# Simple_LED.net
KiCad netlist of a schematic drawn in Altium Designer
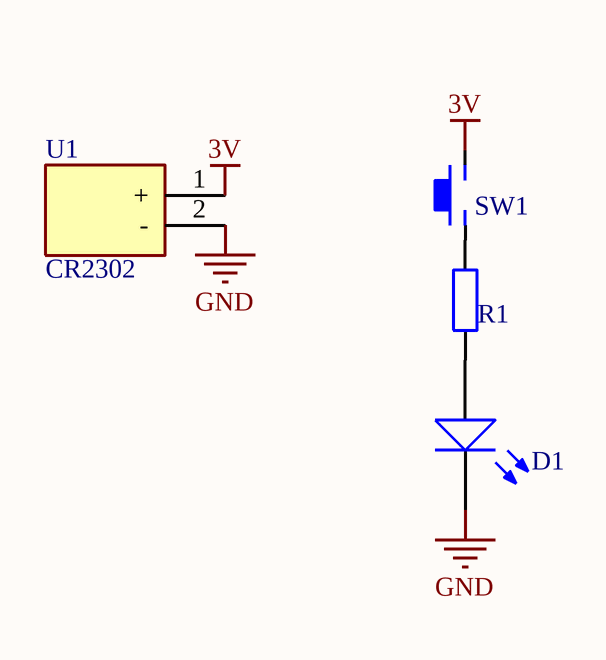
[diagram p0: Simple_LED.SchDoc]

(export (version "E")
  (design (tool "Eeschema 10.0.6"))
  (components
    (comp (ref "D1")
      (value "RED")
      (footprint "LED-0603")
      (description "发光二极管")
      (libsource (lib "Power_Lib_Altium") (part "LED"))
    )
    (comp (ref "R1")
      (value "1R")
      (footprint "R-0603")
      (description "贴片电阻")
      (libsource (lib "Power_Lib_Altium") (part "RES"))
    )
    (comp (ref "SW1")
      (value "KEY")
      (footprint "KEY-4P-4.2*3.4*2.5")
      (description "按键开关")
      (libsource (lib "Power_Lib_Altium") (part "KEY"))
    )
    (comp (ref "U1")
      (value "CR2302")
      (footprint "CR2032-1")
      (description "锂电池")
      (fields (field (name "MANUFACTURER_PART_NUMBER") "1026") (field (name "MOUSER PART NUMBER") "534-1026"))
      (libsource (lib "Power_Lib_Altium") (part "BAT"))
    )
  )
  (nets
    (net (code "1") (name "3V") (class "Default")
      (node (ref "SW1") (pin "2") (pinfunction "2_2") (pintype "passive"))
      (node (ref "U1") (pin "1") (pinfunction "+_1") (pintype "passive"))
    )
    (net (code "2") (name "GND") (class "Default")
      (node (ref "D1") (pin "K") (pinfunction "K_K") (pintype "passive"))
      (node (ref "U1") (pin "2") (pinfunction "-_2") (pintype "passive"))
    )
    (net (code "3") (name "Net-(D1-PadA)") (class "Default")
      (node (ref "D1") (pin "A") (pinfunction "A_A") (pintype "passive"))
      (node (ref "R1") (pin "1") (pinfunction "1_1") (pintype "passive"))
    )
    (net (code "4") (name "Net-(R1-Pad2)") (class "Default")
      (node (ref "R1") (pin "2") (pinfunction "2_2") (pintype "passive"))
      (node (ref "SW1") (pin "1") (pinfunction "1_1") (pintype "passive"))
    )
  )
)
